# ESP32-Controls.net
KiCad netlist of a schematic drawn in Altium Designer
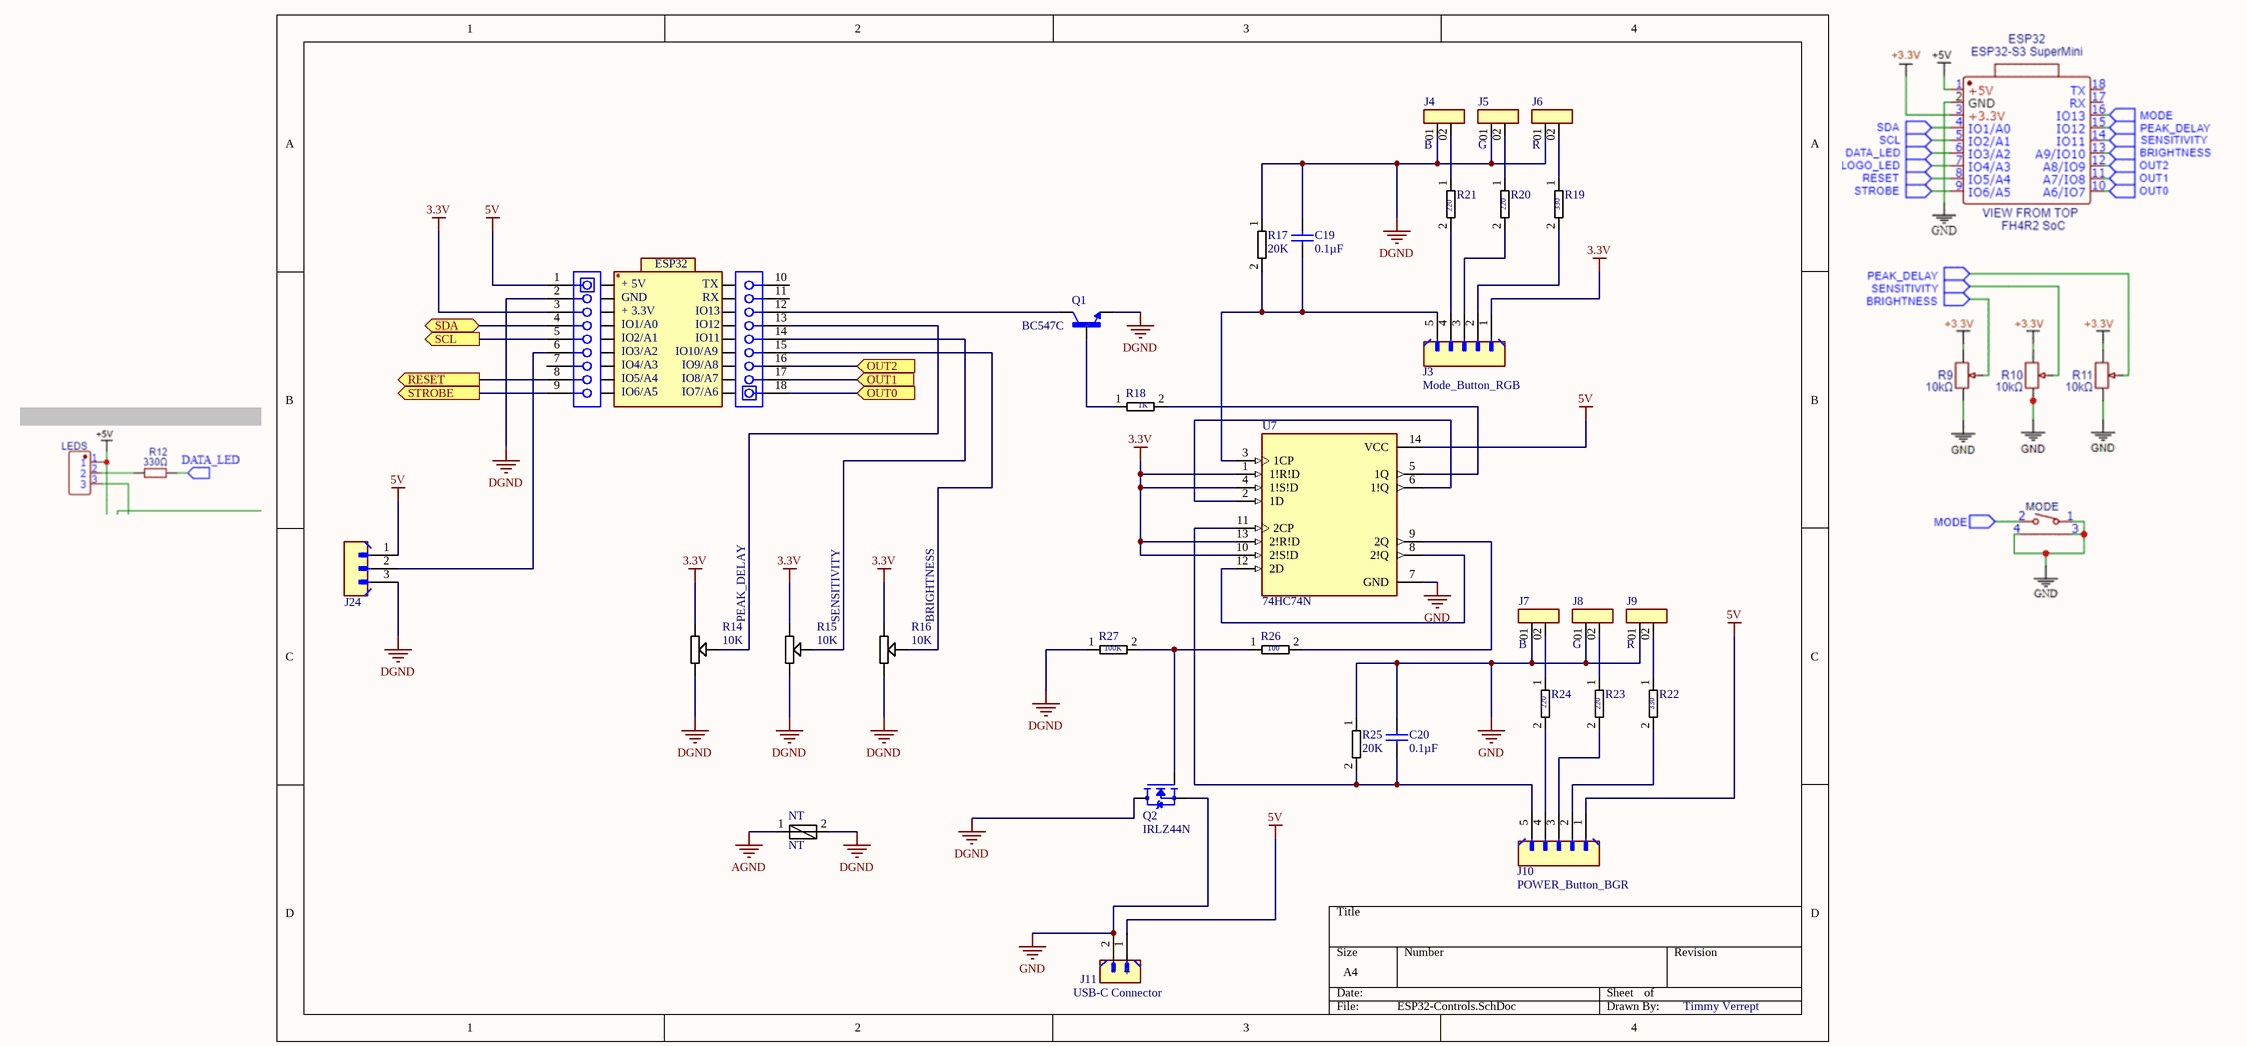
[diagram p0: ESP32-Controls.SchDoc]

(export (version "E")
  (design (tool "Eeschema 10.0.6"))
  (components
    (comp (ref "C19")
      (value "0.1µF")
      (footprint "SMD_CAPACITOR")
      (fields (field (name "MANUFACTURER") "Vitramon") (field (name "PART NUMBER") "VJ0805Y682KXAMT"))
      (libsource (lib "Winnetrie_library") (part "CER Capacitor"))
    )
    (comp (ref "C20")
      (value "0.1µF")
      (footprint "SMD_CAPACITOR")
      (fields (field (name "MANUFACTURER") "Vitramon") (field (name "PART NUMBER") "VJ0805Y682KXAMT"))
      (libsource (lib "Winnetrie_library") (part "CER Capacitor"))
    )
    (comp (ref "ESP32")
      (value "ESP32_Placeholder")
      (footprint "ESP32_placeholder")
      (libsource (lib "Winnetrie_library") (part "ESP32_Placeholder"))
    )
    (comp (ref "J3")
      (value "Mode_Button_RGB")
      (footprint "Connector5P")
      (description "B5B-PH-K-S")
      (fields (field (name "MF") "{'manufacturer': u'JST Sales America Inc.'}"))
      (libsource (lib "Winnetrie_library") (part "Connector_5p"))
    )
    (comp (ref "J4")
      (value "B")
      (footprint "MaleHeader2P")
      (description "Variable Height PCB Header Strips, 0.100 pitch")
      (fields (field (name "MF") "SAMTEC") (field (name "MP") "MTSW-101-09-L-D-210"))
      (libsource (lib "Winnetrie_library") (part "Header_Male2p"))
    )
    (comp (ref "J5")
      (value "G")
      (footprint "MaleHeader2P")
      (description "Variable Height PCB Header Strips, 0.100 pitch")
      (fields (field (name "MF") "SAMTEC") (field (name "MP") "MTSW-101-09-L-D-210"))
      (libsource (lib "Winnetrie_library") (part "Header_Male2p"))
    )
    (comp (ref "J6")
      (value "R")
      (footprint "MaleHeader2P")
      (description "Variable Height PCB Header Strips, 0.100 pitch")
      (fields (field (name "MF") "SAMTEC") (field (name "MP") "MTSW-101-09-L-D-210"))
      (libsource (lib "Winnetrie_library") (part "Header_Male2p"))
    )
    (comp (ref "J7")
      (value "B")
      (footprint "MaleHeader2P")
      (description "Variable Height PCB Header Strips, 0.100 pitch")
      (fields (field (name "MF") "SAMTEC") (field (name "MP") "MTSW-101-09-L-D-210"))
      (libsource (lib "Winnetrie_library") (part "Header_Male2p"))
    )
    (comp (ref "J8")
      (value "G")
      (footprint "MaleHeader2P")
      (description "Variable Height PCB Header Strips, 0.100 pitch")
      (fields (field (name "MF") "SAMTEC") (field (name "MP") "MTSW-101-09-L-D-210"))
      (libsource (lib "Winnetrie_library") (part "Header_Male2p"))
    )
    (comp (ref "J9")
      (value "R")
      (footprint "MaleHeader2P")
      (description "Variable Height PCB Header Strips, 0.100 pitch")
      (fields (field (name "MF") "SAMTEC") (field (name "MP") "MTSW-101-09-L-D-210"))
      (libsource (lib "Winnetrie_library") (part "Header_Male2p"))
    )
    (comp (ref "J10")
      (value "POWER_Button_BGR")
      (footprint "Connector5P")
      (description "B5B-PH-K-S")
      (fields (field (name "MF") "{'manufacturer': u'JST Sales America Inc.'}"))
      (libsource (lib "Winnetrie_library") (part "Connector_5p"))
    )
    (comp (ref "J11")
      (value "USB-C Connector")
      (footprint "JST_B2B-PH-K-S")
      (description "Connector Header Through Hole 2 position 0.079 (2.00mm)B2B-PH-K-S")
      (fields (field (name "MF") "JST Sales America Inc.") (field (name "MP") "B2B-PH-K-S"))
      (libsource (lib "Winnetrie_library") (part "Connector_2p"))
    )
    (comp (ref "J24")
      (value "B3B-PH-K-S")
      (footprint "Connector3P")
      (fields (field (name "MF") "{'manufacturer': u'JST Sales America Inc.'}"))
      (libsource (lib "Winnetrie_library") (part "Connector_3p"))
    )
    (comp (ref "NT") (value "NT") (footprint "NT") (libsource (lib "Winnetrie_library") (part "NT")))
    (comp (ref "Q1")
      (value "BC547C")
      (footprint "Transistor")
      (description "BJT, TO-92, 45V, 100mA, NPN, 0.5W, 150Â°C")
      (fields (field (name "MF") "Diotec Semiconductor"))
      (libsource (lib "Winnetrie_library") (part "BC547C"))
    )
    (comp (ref "Q2")
      (value "IRLZ44N")
      (footprint "MOSFET")
      (description "N-Channel 55 V 47A (Tc) 3.8W (Ta), 110W (Tc) Surface Mount D2PAK")
      (fields (field (name "MF") "Infineon / IR"))
      (libsource (lib "Winnetrie_library") (part "IRLZ44N"))
    )
    (comp (ref "R14")
      (value "10K")
      (footprint "POTENTIOMETER")
      (description "16mm Rotary Potentiometers\r\nWH148-1A-2-18T-L20")
      (fields (field (name "MF") "Kls electronics") (field (name "MP") "WH148-1A-2-18T-L20"))
      (libsource (lib "Winnetrie_library") (part "Potmeter"))
    )
    (comp (ref "R15")
      (value "10K")
      (footprint "POTENTIOMETER")
      (description "16mm Rotary Potentiometers\r\nWH148-1A-2-18T-L20")
      (fields (field (name "MF") "Kls electronics") (field (name "MP") "WH148-1A-2-18T-L20"))
      (libsource (lib "Winnetrie_library") (part "Potmeter"))
    )
    (comp (ref "R16")
      (value "10K")
      (footprint "POTENTIOMETER")
      (description "16mm Rotary Potentiometers\r\nWH148-1A-2-18T-L20")
      (fields (field (name "MF") "Kls electronics") (field (name "MP") "WH148-1A-2-18T-L20"))
      (libsource (lib "Winnetrie_library") (part "Potmeter"))
    )
    (comp (ref "R17")
      (value "20K")
      (footprint "SMD_RESISTOR")
      (description "RES SMD 681 OHM 0.1% 1/8W 0805")
      (fields
        (field (name "MANUFACTURER") "Yageo")
        (field (name "MANUFACTURER PART NUMBER") "RT0805BRD07681RL")
      )
      (libsource (lib "Winnetrie_library") (part "Resistor"))
    )
    (comp (ref "R18")
      (value "1K")
      (footprint "SMD_RESISTOR")
      (description "RES SMD 681 OHM 0.1% 1/8W 0805")
      (fields
        (field (name "MANUFACTURER") "Yageo")
        (field (name "MANUFACTURER PART NUMBER") "RT0805BRD07681RL")
      )
      (libsource (lib "Winnetrie_library") (part "Resistor"))
    )
    (comp (ref "R19")
      (value "330")
      (footprint "SMD_RESISTOR")
      (description "RES SMD 681 OHM 0.1% 1/8W 0805")
      (fields
        (field (name "MANUFACTURER") "Yageo")
        (field (name "MANUFACTURER PART NUMBER") "RT0805BRD07681RL")
      )
      (libsource (lib "Winnetrie_library") (part "Resistor"))
    )
    (comp (ref "R20")
      (value "220")
      (footprint "SMD_RESISTOR")
      (description "RES SMD 681 OHM 0.1% 1/8W 0805")
      (fields
        (field (name "MANUFACTURER") "Yageo")
        (field (name "MANUFACTURER PART NUMBER") "RT0805BRD07681RL")
      )
      (libsource (lib "Winnetrie_library") (part "Resistor"))
    )
    (comp (ref "R21")
      (value "220")
      (footprint "SMD_RESISTOR")
      (description "RES SMD 681 OHM 0.1% 1/8W 0805")
      (fields
        (field (name "MANUFACTURER") "Yageo")
        (field (name "MANUFACTURER PART NUMBER") "RT0805BRD07681RL")
      )
      (libsource (lib "Winnetrie_library") (part "Resistor"))
    )
    (comp (ref "R22")
      (value "330")
      (footprint "SMD_RESISTOR")
      (description "RES SMD 681 OHM 0.1% 1/8W 0805")
      (fields
        (field (name "MANUFACTURER") "Yageo")
        (field (name "MANUFACTURER PART NUMBER") "RT0805BRD07681RL")
      )
      (libsource (lib "Winnetrie_library") (part "Resistor"))
    )
    (comp (ref "R23")
      (value "220")
      (footprint "SMD_RESISTOR")
      (description "RES SMD 681 OHM 0.1% 1/8W 0805")
      (fields
        (field (name "MANUFACTURER") "Yageo")
        (field (name "MANUFACTURER PART NUMBER") "RT0805BRD07681RL")
      )
      (libsource (lib "Winnetrie_library") (part "Resistor"))
    )
    (comp (ref "R24")
      (value "220")
      (footprint "SMD_RESISTOR")
      (description "RES SMD 681 OHM 0.1% 1/8W 0805")
      (fields
        (field (name "MANUFACTURER") "Yageo")
        (field (name "MANUFACTURER PART NUMBER") "RT0805BRD07681RL")
      )
      (libsource (lib "Winnetrie_library") (part "Resistor"))
    )
    (comp (ref "R25")
      (value "20K")
      (footprint "SMD_RESISTOR")
      (description "RES SMD 681 OHM 0.1% 1/8W 0805")
      (fields
        (field (name "MANUFACTURER") "Yageo")
        (field (name "MANUFACTURER PART NUMBER") "RT0805BRD07681RL")
      )
      (libsource (lib "Winnetrie_library") (part "Resistor"))
    )
    (comp (ref "R26")
      (value "100")
      (footprint "SMD_RESISTOR")
      (description "RES SMD 681 OHM 0.1% 1/8W 0805")
      (fields
        (field (name "MANUFACTURER") "Yageo")
        (field (name "MANUFACTURER PART NUMBER") "RT0805BRD07681RL")
      )
      (libsource (lib "Winnetrie_library") (part "Resistor"))
    )
    (comp (ref "R27")
      (value "100K")
      (footprint "SMD_RESISTOR")
      (description "RES SMD 681 OHM 0.1% 1/8W 0805")
      (fields
        (field (name "MANUFACTURER") "Yageo")
        (field (name "MANUFACTURER PART NUMBER") "RT0805BRD07681RL")
      )
      (libsource (lib "Winnetrie_library") (part "Resistor"))
    )
    (comp (ref "U7")
      (value "74HC74N")
      (footprint "74HC74")
      (description "D FLIP-FLOP")
      (fields (field (name "MF") "Rochester Electronics, LLC") (field (name "MP") "74HC74N,652"))
      (libsource (lib "Winnetrie_library") (part "74HC74N,652"))
    )
  )
  (nets
    (net (code "1") (name "/OUT0") (class "Default")
      (node (ref "ESP32") (pin "18") (pinfunction "18_18") (pintype "passive"))
    )
    (net (code "2") (name "/OUT1") (class "Default")
      (node (ref "ESP32") (pin "17") (pinfunction "17_17") (pintype "passive"))
    )
    (net (code "3") (name "/OUT2") (class "Default")
      (node (ref "ESP32") (pin "16") (pinfunction "16_16") (pintype "passive"))
    )
    (net (code "4") (name "/RESET") (class "Default")
      (node (ref "ESP32") (pin "8") (pinfunction "8_8") (pintype "passive"))
    )
    (net (code "5") (name "/SCL") (class "Default")
      (node (ref "ESP32") (pin "5") (pinfunction "5_5") (pintype "passive"))
    )
    (net (code "6") (name "/SDA") (class "Default")
      (node (ref "ESP32") (pin "4") (pinfunction "4_4") (pintype "passive"))
    )
    (net (code "7") (name "/STROBE") (class "Default")
      (node (ref "ESP32") (pin "9") (pinfunction "9_9") (pintype "passive"))
    )
    (net (code "8") (name "3.3V") (class "Default")
      (node (ref "ESP32") (pin "3") (pinfunction "3_3") (pintype "passive"))
      (node (ref "J3") (pin "1") (pinfunction "1_1") (pintype "passive"))
      (node (ref "R14") (pin "3") (pinfunction "3_3") (pintype "passive"))
      (node (ref "R15") (pin "3") (pinfunction "3_3") (pintype "passive"))
      (node (ref "R16") (pin "3") (pinfunction "3_3") (pintype "passive"))
      (node (ref "U7") (pin "1") (pinfunction "1!R!D_1") (pintype "input"))
      (node (ref "U7") (pin "10") (pinfunction "2!S!D_10") (pintype "input"))
      (node (ref "U7") (pin "13") (pinfunction "2!R!D_13") (pintype "input"))
      (node (ref "U7") (pin "4") (pinfunction "1!S!D_4") (pintype "input"))
    )
    (net (code "9") (name "5V") (class "Default")
      (node (ref "ESP32") (pin "1") (pinfunction "1_1") (pintype "passive"))
      (node (ref "J10") (pin "1") (pinfunction "1_1") (pintype "passive"))
      (node (ref "J11") (pin "1") (pinfunction "+_1") (pintype "passive"))
      (node (ref "J24") (pin "1") (pinfunction "1_1") (pintype "passive"))
      (node (ref "U7") (pin "14") (pinfunction "VCC_14") (pintype "power_in"))
    )
    (net (code "10") (name "AGND") (class "Default")
      (node (ref "NT") (pin "1") (pinfunction "1_1") (pintype "passive"))
    )
    (net (code "11") (name "DGND") (class "Default")
      (node (ref "C19") (pin "1") (pinfunction "1_1") (pintype "passive"))
      (node (ref "ESP32") (pin "2") (pinfunction "2_2") (pintype "passive"))
      (node (ref "J24") (pin "3") (pinfunction "3_3") (pintype "passive"))
      (node (ref "J4") (pin "01") (pinfunction "01_01") (pintype "passive"))
      (node (ref "J5") (pin "01") (pinfunction "01_01") (pintype "passive"))
      (node (ref "J6") (pin "01") (pinfunction "01_01") (pintype "passive"))
      (node (ref "NT") (pin "2") (pinfunction "2_2") (pintype "passive"))
      (node (ref "Q1") (pin "3") (pinfunction "E_3") (pintype "passive"))
      (node (ref "Q2") (pin "2") (pinfunction "D_2") (pintype "passive"))
      (node (ref "R14") (pin "1") (pinfunction "1_1") (pintype "passive"))
      (node (ref "R15") (pin "1") (pinfunction "1_1") (pintype "passive"))
      (node (ref "R16") (pin "1") (pinfunction "1_1") (pintype "passive"))
      (node (ref "R17") (pin "1") (pinfunction "1_1") (pintype "passive"))
      (node (ref "R27") (pin "1") (pinfunction "1_1") (pintype "passive"))
    )
    (net (code "12") (name "GND") (class "Default")
      (node (ref "C20") (pin "1") (pinfunction "1_1") (pintype "passive"))
      (node (ref "J11") (pin "2") (pinfunction "-_2") (pintype "passive"))
      (node (ref "J7") (pin "01") (pinfunction "01_01") (pintype "passive"))
      (node (ref "J8") (pin "01") (pinfunction "01_01") (pintype "passive"))
      (node (ref "J9") (pin "01") (pinfunction "01_01") (pintype "passive"))
      (node (ref "Q2") (pin "3") (pinfunction "S_3") (pintype "passive"))
      (node (ref "R25") (pin "1") (pinfunction "1_1") (pintype "passive"))
      (node (ref "U7") (pin "7") (pinfunction "GND_7") (pintype "power_in"))
    )
    (net (code "13") (name "Net-(ESP32-Pad6)") (class "Default")
      (node (ref "ESP32") (pin "6") (pinfunction "6_6") (pintype "passive"))
      (node (ref "J24") (pin "2") (pinfunction "2_2") (pintype "passive"))
    )
    (net (code "14") (name "Net-(ESP32-Pad13)") (class "Default")
      (node (ref "ESP32") (pin "13") (pinfunction "13_13") (pintype "passive"))
      (node (ref "R14") (pin "2") (pinfunction "2_2") (pintype "passive"))
    )
    (net (code "15") (name "Net-(ESP32-Pad14)") (class "Default")
      (node (ref "ESP32") (pin "14") (pinfunction "14_14") (pintype "passive"))
      (node (ref "R15") (pin "2") (pinfunction "2_2") (pintype "passive"))
    )
    (net (code "16") (name "Net-(ESP32-Pad15)") (class "Default")
      (node (ref "ESP32") (pin "15") (pinfunction "15_15") (pintype "passive"))
      (node (ref "R16") (pin "2") (pinfunction "2_2") (pintype "passive"))
    )
    (net (code "17") (name "Net-(J3-Pad2)") (class "Default")
      (node (ref "J3") (pin "2") (pinfunction "2_2") (pintype "passive"))
      (node (ref "R19") (pin "2") (pinfunction "2_2") (pintype "passive"))
    )
    (net (code "18") (name "Net-(J3-Pad3)") (class "Default")
      (node (ref "J3") (pin "3") (pinfunction "3_3") (pintype "passive"))
      (node (ref "R20") (pin "2") (pinfunction "2_2") (pintype "passive"))
    )
    (net (code "19") (name "Net-(J3-Pad4)") (class "Default")
      (node (ref "J3") (pin "4") (pinfunction "4_4") (pintype "passive"))
      (node (ref "R21") (pin "2") (pinfunction "2_2") (pintype "passive"))
    )
    (net (code "20") (name "Net-(J4-Pad02)") (class "Default")
      (node (ref "J4") (pin "02") (pinfunction "02_02") (pintype "passive"))
      (node (ref "R21") (pin "1") (pinfunction "1_1") (pintype "passive"))
    )
    (net (code "21") (name "Net-(J5-Pad02)") (class "Default")
      (node (ref "J5") (pin "02") (pinfunction "02_02") (pintype "passive"))
      (node (ref "R20") (pin "1") (pinfunction "1_1") (pintype "passive"))
    )
    (net (code "22") (name "Net-(J6-Pad02)") (class "Default")
      (node (ref "J6") (pin "02") (pinfunction "02_02") (pintype "passive"))
      (node (ref "R19") (pin "1") (pinfunction "1_1") (pintype "passive"))
    )
    (net (code "23") (name "Net-(J7-Pad02)") (class "Default")
      (node (ref "J7") (pin "02") (pinfunction "02_02") (pintype "passive"))
      (node (ref "R24") (pin "1") (pinfunction "1_1") (pintype "passive"))
    )
    (net (code "24") (name "Net-(J8-Pad02)") (class "Default")
      (node (ref "J8") (pin "02") (pinfunction "02_02") (pintype "passive"))
      (node (ref "R23") (pin "1") (pinfunction "1_1") (pintype "passive"))
    )
    (net (code "25") (name "Net-(J9-Pad02)") (class "Default")
      (node (ref "J9") (pin "02") (pinfunction "02_02") (pintype "passive"))
      (node (ref "R22") (pin "1") (pinfunction "1_1") (pintype "passive"))
    )
    (net (code "26") (name "Net-(J10-Pad2)") (class "Default")
      (node (ref "J10") (pin "2") (pinfunction "2_2") (pintype "passive"))
      (node (ref "R22") (pin "2") (pinfunction "2_2") (pintype "passive"))
    )
    (net (code "27") (name "Net-(J10-Pad3)") (class "Default")
      (node (ref "J10") (pin "3") (pinfunction "3_3") (pintype "passive"))
      (node (ref "R23") (pin "2") (pinfunction "2_2") (pintype "passive"))
    )
    (net (code "28") (name "Net-(J10-Pad4)") (class "Default")
      (node (ref "J10") (pin "4") (pinfunction "4_4") (pintype "passive"))
      (node (ref "R24") (pin "2") (pinfunction "2_2") (pintype "passive"))
    )
    (net (code "29") (name "Net-(Q1-B)") (class "Default")
      (node (ref "Q1") (pin "2") (pinfunction "B_2") (pintype "passive"))
      (node (ref "R18") (pin "1") (pinfunction "1_1") (pintype "passive"))
    )
    (net (code "30") (name "Net-(Q1-C)") (class "Default")
      (node (ref "ESP32") (pin "12") (pinfunction "12_12") (pintype "passive"))
      (node (ref "Q1") (pin "1") (pinfunction "C_1") (pintype "passive"))
    )
    (net (code "31") (name "Net-(Q2-G)") (class "Default")
      (node (ref "Q2") (pin "1") (pinfunction "G_1") (pintype "passive"))
      (node (ref "R26") (pin "1") (pinfunction "1_1") (pintype "passive"))
      (node (ref "R27") (pin "2") (pinfunction "2_2") (pintype "passive"))
    )
    (net (code "32") (name "Net-(U7-1!Q)") (class "Default")
      (node (ref "U7") (pin "2") (pinfunction "1D_2") (pintype "input"))
      (node (ref "U7") (pin "6") (pinfunction "1!Q_6") (pintype "output"))
    )
    (net (code "33") (name "Net-(U7-1CP)") (class "Default")
      (node (ref "C19") (pin "2") (pinfunction "2_2") (pintype "passive"))
      (node (ref "J3") (pin "5") (pinfunction "5_5") (pintype "passive"))
      (node (ref "R17") (pin "2") (pinfunction "2_2") (pintype "passive"))
      (node (ref "U7") (pin "3") (pinfunction "1CP_3") (pintype "input"))
    )
    (net (code "34") (name "Net-(U7-1Q)") (class "Default")
      (node (ref "R18") (pin "2") (pinfunction "2_2") (pintype "passive"))
      (node (ref "U7") (pin "5") (pinfunction "1Q_5") (pintype "output"))
    )
    (net (code "35") (name "Net-(U7-2!Q)") (class "Default")
      (node (ref "U7") (pin "12") (pinfunction "2D_12") (pintype "input"))
      (node (ref "U7") (pin "8") (pinfunction "2!Q_8") (pintype "output"))
    )
    (net (code "36") (name "Net-(U7-2CP)") (class "Default")
      (node (ref "C20") (pin "2") (pinfunction "2_2") (pintype "passive"))
      (node (ref "J10") (pin "5") (pinfunction "5_5") (pintype "passive"))
      (node (ref "R25") (pin "2") (pinfunction "2_2") (pintype "passive"))
      (node (ref "U7") (pin "11") (pinfunction "2CP_11") (pintype "input"))
    )
    (net (code "37") (name "Net-(U7-2Q)") (class "Default")
      (node (ref "R26") (pin "2") (pinfunction "2_2") (pintype "passive"))
      (node (ref "U7") (pin "9") (pinfunction "2Q_9") (pintype "output"))
    )
    (net (code "38") (name "unconnected-(ESP32-Pad7)") (class "Default")
      (node (ref "ESP32") (pin "7") (pinfunction "7_7") (pintype "passive"))
    )
    (net (code "39") (name "unconnected-(ESP32-Pad10)") (class "Default")
      (node (ref "ESP32") (pin "10") (pinfunction "10_10") (pintype "passive"))
    )
    (net (code "40") (name "unconnected-(ESP32-Pad11)") (class "Default")
      (node (ref "ESP32") (pin "11") (pinfunction "11_11") (pintype "passive"))
    )
  )
)
